# Safety_Loop.net
KiCad netlist of a schematic drawn in Altium Designer
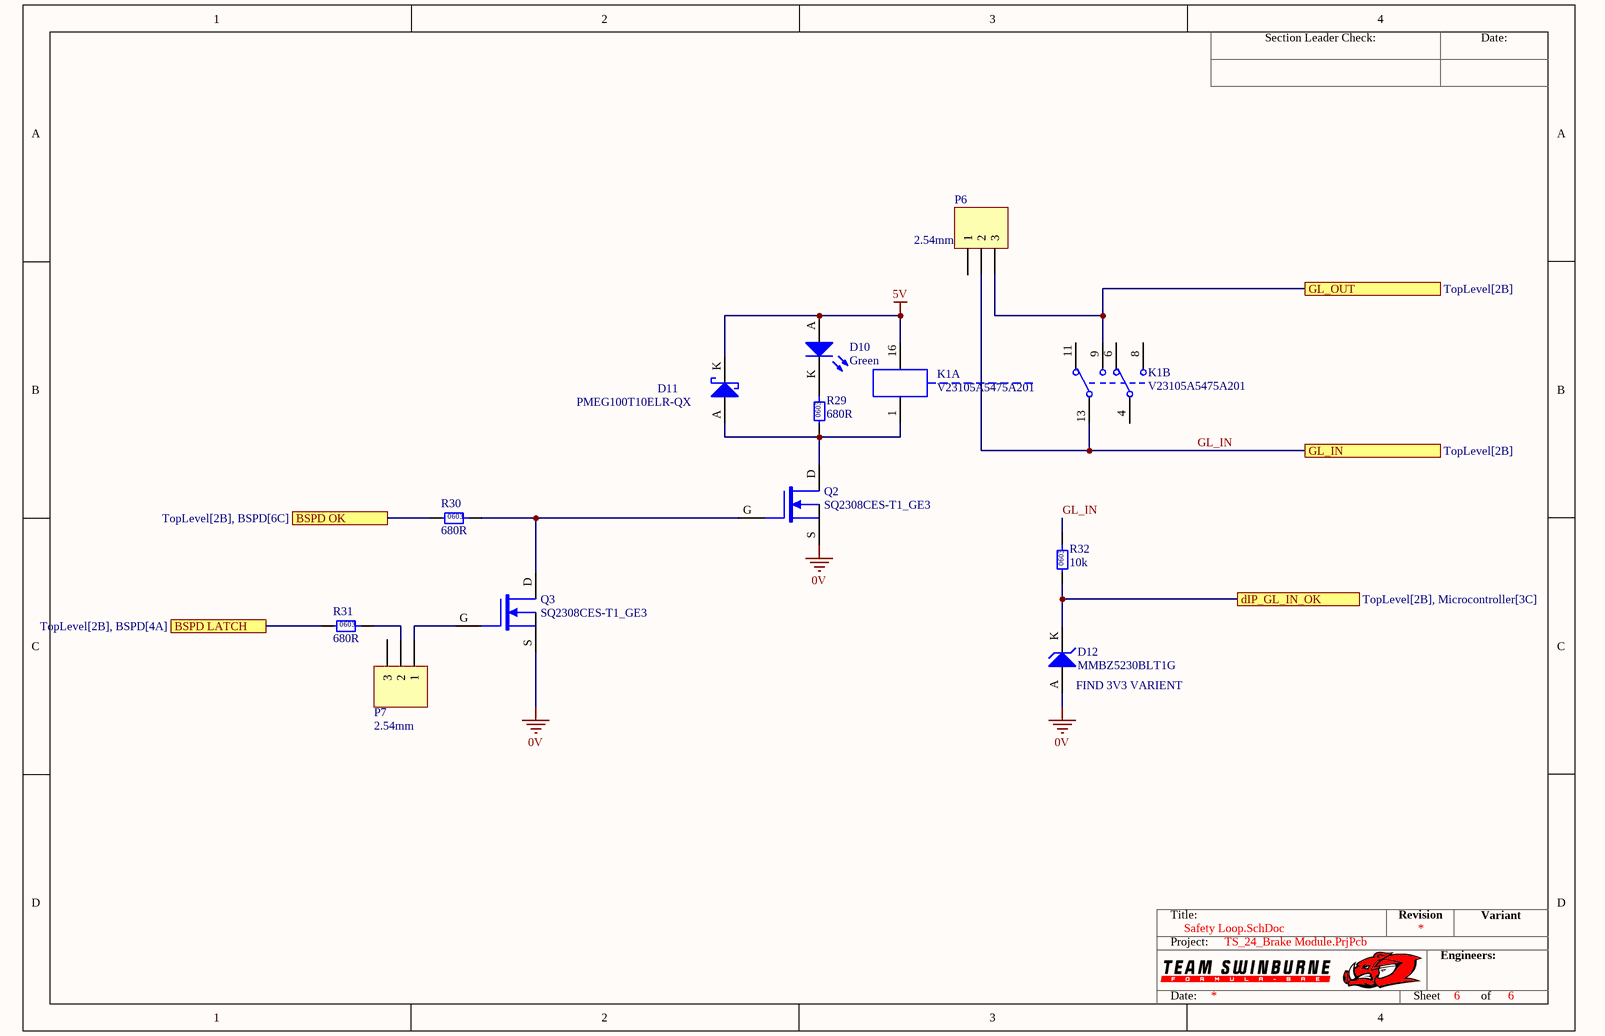
[diagram p0: Safety Loop.SchDoc]

(export (version "E")
  (design (tool "Eeschema 10.0.6"))
  (components
    (comp (ref "D10")
      (value "Green")
      (footprint "0805 LED")
      (description "Green LED Indication - Discrete 1.75V 0805 (2012 Metric)")
      (fields (field (name "PART NUMBER") "SML-210FTT86") (field (name "MANUFACTURER") "ROHM Semiconductor"))
      (libsource (lib "ts_standard_library") (part "LED"))
    )
    (comp (ref "D11")
      (value "PMEG100T10ELR-QX")
      (footprint "NXP SOD123W")
      (fields
        (field (name "MANUFACTURER") "Nexperia USA Inc.")
        (field (name "DIGIKEY PART NUMBER") "1727-PMEG100T10ELR-QXCT-ND")
      )
      (libsource (lib "ts_standard_library") (part "Diode (Schottky)"))
    )
    (comp (ref "D12")
      (value "MMBZ5230BLT1G")
      (footprint "NEXPERIA_SOT23")
      (fields
        (field (name "MANUFACTURER") "onsemi")
        (field (name "DIGIKEY PART NUMBER") "MMBZ5230BLT1GOSTR-ND")
      )
      (libsource (lib "ts_standard_library") (part "Zener Diode"))
    )
    (comp (ref "K1")
      (value "V23105A5475A201")
      (footprint "TI 2-DIL")
      (description "5V DPDT Relay 3A 220VDC")
      (fields (field (name "MANUFACTURER") "Axicom") (field (name "DIGIKEY PART NUMBER") "PB383-ND"))
      (libsource (lib "ts_standard_library") (part "V23105A5475A201"))
    )
    (comp (ref "P6")
      (value "2.54mm")
      (footprint "TH 2.54mm Header 1x3")
      (fields (field (name "PART NUMBER") "TH 2.54mm Header 1x3") (field (name "CONTACT") "NA"))
      (libsource (lib "ts_standard_connectors") (part "Header 1x3"))
    )
    (comp (ref "P7")
      (value "2.54mm")
      (footprint "TH 2.54mm Header 1x3")
      (fields (field (name "PART NUMBER") "TH 2.54mm Header 1x3") (field (name "CONTACT") "NA"))
      (libsource (lib "") (part "Header 1x3_1"))
    )
    (comp (ref "Q2")
      (value "SQ2308CES-T1_GE3")
      (footprint "VSHY SOT-23-3")
      (description "MOSFET N-CH 60V 2.3A SOT23")
      (fields
        (field (name "MANUFACTURER") "Vishay Siliconix")
        (field (name "DIGIKEY PART NUMBER") "SQ2308CES-T1_GE3CT-ND")
        (field (name "PUBLISHER") "Altium Limited")
      )
      (libsource (lib "ts_standard_library") (part "MOSFET-N"))
    )
    (comp (ref "Q3")
      (value "SQ2308CES-T1_GE3")
      (footprint "VSHY SOT-23-3")
      (description "MOSFET N-CH 60V 2.3A SOT23")
      (fields
        (field (name "MANUFACTURER") "Vishay Siliconix")
        (field (name "DIGIKEY PART NUMBER") "SQ2308CES-T1_GE3CT-ND")
        (field (name "PUBLISHER") "Altium Limited")
      )
      (libsource (lib "ts_standard_library") (part "MOSFET-N"))
    )
    (comp (ref "R29")
      (value "680R")
      (footprint "0603")
      (fields
        (field (name "PART NUMBER") "RC0603JR-13680RL")
        (field (name "MANUFACTURER") "YAGEO")
        (field (name "TOLERANCE") "0.01")
      )
      (libsource (lib "ts_standard_library") (part "Resistor 0603"))
    )
    (comp (ref "R30")
      (value "680R")
      (footprint "0603")
      (fields
        (field (name "PART NUMBER") "RC0603JR-13680RL")
        (field (name "MANUFACTURER") "YAGEO")
        (field (name "TOLERANCE") "0.01")
      )
      (libsource (lib "ts_standard_library") (part "Resistor 0603"))
    )
    (comp (ref "R31")
      (value "680R")
      (footprint "0603")
      (fields
        (field (name "PART NUMBER") "RC0603JR-13680RL")
        (field (name "MANUFACTURER") "YAGEO")
        (field (name "TOLERANCE") "0.01")
      )
      (libsource (lib "ts_standard_library") (part "Resistor 0603"))
    )
    (comp (ref "R32")
      (value "10k")
      (footprint "0603")
      (fields
        (field (name "PART NUMBER") "RC0603FR-0710KL")
        (field (name "MANUFACTURER") "YAGEO")
        (field (name "TOLERANCE") "0.01")
      )
      (libsource (lib "ts_standard_library") (part "Resistor 0603"))
    )
  )
  (nets
    (net (code "1") (name "/BSPD LATCH") (class "Default")
      (node (ref "R31") (pin "1") (pinfunction "1_1") (pintype "passive"))
    )
    (net (code "2") (name "/BSPD OK") (class "Default")
      (node (ref "R30") (pin "1") (pinfunction "1_1") (pintype "passive"))
    )
    (net (code "3") (name "/GL_IN") (class "Default")
      (node (ref "K1") (pin "13") (pinfunction "13_13") (pintype "passive"))
      (node (ref "P6") (pin "2") (pinfunction "2_2") (pintype "passive"))
      (node (ref "R32") (pin "2") (pinfunction "2_2") (pintype "passive"))
    )
    (net (code "4") (name "/GL_OUT") (class "Default")
      (node (ref "K1") (pin "9") (pinfunction "9_9") (pintype "passive"))
      (node (ref "P6") (pin "3") (pinfunction "3_3") (pintype "passive"))
    )
    (net (code "5") (name "/dIP_GL_IN_OK") (class "Default")
      (node (ref "D12") (pin "K") (pinfunction "K_K") (pintype "passive"))
      (node (ref "R32") (pin "1") (pinfunction "1_1") (pintype "passive"))
    )
    (net (code "6") (name "0V") (class "Default")
      (node (ref "D12") (pin "A") (pinfunction "A_A") (pintype "passive"))
      (node (ref "Q2") (pin "S") (pinfunction "S_S") (pintype "passive"))
      (node (ref "Q3") (pin "S") (pinfunction "S_S") (pintype "passive"))
    )
    (net (code "7") (name "5V") (class "Default")
      (node (ref "D10") (pin "A") (pinfunction "A_A") (pintype "passive"))
      (node (ref "D11") (pin "K") (pinfunction "K_K") (pintype "passive"))
      (node (ref "K1") (pin "16") (pinfunction "16_16") (pintype "passive"))
    )
    (net (code "8") (name "Net-(D10-PadK)") (class "Default")
      (node (ref "D10") (pin "K") (pinfunction "K_K") (pintype "passive"))
      (node (ref "R29") (pin "2") (pinfunction "2_2") (pintype "passive"))
    )
    (net (code "9") (name "Net-(D11-PadA)") (class "Default")
      (node (ref "D11") (pin "A") (pinfunction "A_A") (pintype "passive"))
      (node (ref "K1") (pin "1") (pinfunction "1_1") (pintype "passive"))
      (node (ref "Q2") (pin "D") (pinfunction "D_D") (pintype "passive"))
      (node (ref "R29") (pin "1") (pinfunction "1_1") (pintype "passive"))
    )
    (net (code "10") (name "Net-(P7-Pad1)") (class "Default")
      (node (ref "P7") (pin "1") (pinfunction "1_1") (pintype "passive"))
      (node (ref "Q3") (pin "G") (pinfunction "G_G") (pintype "passive"))
    )
    (net (code "11") (name "Net-(P7-Pad2)") (class "Default")
      (node (ref "P7") (pin "2") (pinfunction "2_2") (pintype "passive"))
      (node (ref "R31") (pin "2") (pinfunction "2_2") (pintype "passive"))
    )
    (net (code "12") (name "Net-(Q2-PadG)") (class "Default")
      (node (ref "Q2") (pin "G") (pinfunction "G_G") (pintype "passive"))
      (node (ref "Q3") (pin "D") (pinfunction "D_D") (pintype "passive"))
      (node (ref "R30") (pin "2") (pinfunction "2_2") (pintype "passive"))
    )
    (net (code "13") (name "unconnected-(K1-Pad4)") (class "Default")
      (node (ref "K1") (pin "4") (pinfunction "4_4") (pintype "passive"))
    )
    (net (code "14") (name "unconnected-(K1-Pad6)") (class "Default")
      (node (ref "K1") (pin "6") (pinfunction "6_6") (pintype "passive"))
    )
    (net (code "15") (name "unconnected-(K1-Pad8)") (class "Default")
      (node (ref "K1") (pin "8") (pinfunction "8_8") (pintype "passive"))
    )
    (net (code "16") (name "unconnected-(K1-Pad11)") (class "Default")
      (node (ref "K1") (pin "11") (pinfunction "11_11") (pintype "passive"))
    )
    (net (code "17") (name "unconnected-(P6-Pad1)") (class "Default")
      (node (ref "P6") (pin "1") (pinfunction "1_1") (pintype "passive"))
    )
    (net (code "18") (name "unconnected-(P7-Pad3)") (class "Default")
      (node (ref "P7") (pin "3") (pinfunction "3_3") (pintype "passive"))
    )
  )
)
